# Sheet4.net
KiCad netlist of a schematic drawn in Altium Designer
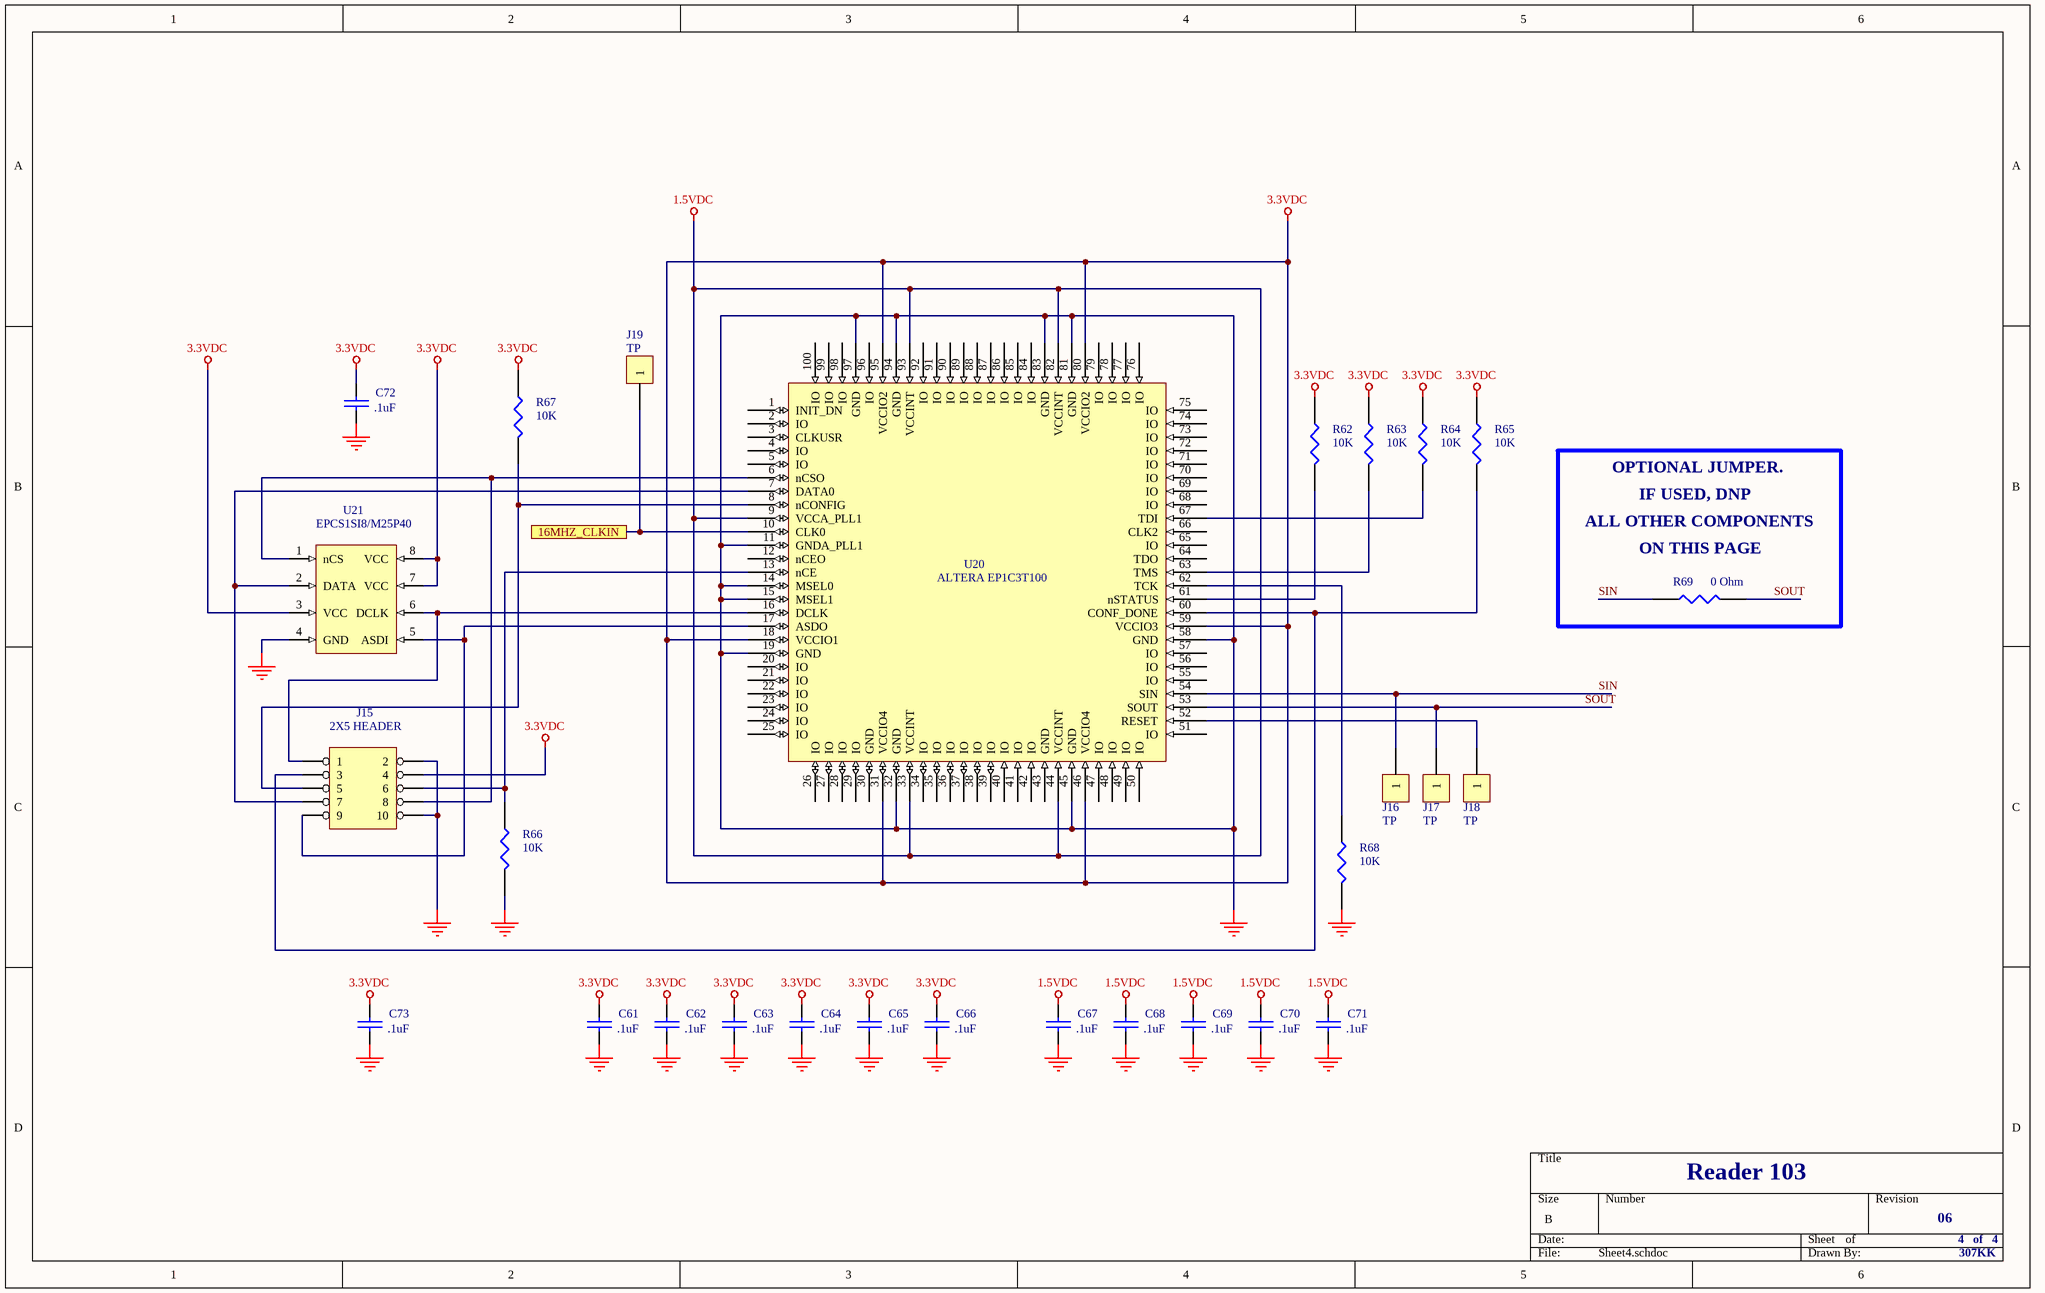
[diagram p0: Sheet4.schdoc]

(export (version "E")
  (design (tool "Eeschema 10.0.6"))
  (components
    (comp (ref "C61")
      (value ".1uF")
      (footprint "0603")
      (description "Capacitor")
      (libsource (lib "*") (part "CAP"))
    )
    (comp (ref "C62")
      (value ".1uF")
      (footprint "0603")
      (description "Capacitor")
      (libsource (lib "*") (part "CAP"))
    )
    (comp (ref "C63")
      (value ".1uF")
      (footprint "0603")
      (description "Capacitor")
      (libsource (lib "*") (part "CAP"))
    )
    (comp (ref "C64")
      (value ".1uF")
      (footprint "0603")
      (description "Capacitor")
      (libsource (lib "*") (part "CAP"))
    )
    (comp (ref "C65")
      (value ".1uF")
      (footprint "0603")
      (description "Capacitor")
      (libsource (lib "*") (part "CAP"))
    )
    (comp (ref "C66")
      (value ".1uF")
      (footprint "0603")
      (description "Capacitor")
      (libsource (lib "*") (part "CAP"))
    )
    (comp (ref "C67")
      (value ".1uF")
      (footprint "0603")
      (description "Capacitor")
      (libsource (lib "*") (part "CAP"))
    )
    (comp (ref "C68")
      (value ".1uF")
      (footprint "0603")
      (description "Capacitor")
      (libsource (lib "*") (part "CAP"))
    )
    (comp (ref "C69")
      (value ".1uF")
      (footprint "0603")
      (description "Capacitor")
      (libsource (lib "*") (part "CAP"))
    )
    (comp (ref "C70")
      (value ".1uF")
      (footprint "0603")
      (description "Capacitor")
      (libsource (lib "*") (part "CAP"))
    )
    (comp (ref "C71")
      (value ".1uF")
      (footprint "0603")
      (description "Capacitor")
      (libsource (lib "*") (part "CAP"))
    )
    (comp (ref "C72")
      (value ".1uF")
      (footprint "0603")
      (description "Capacitor")
      (libsource (lib "*") (part "CAP"))
    )
    (comp (ref "C73")
      (value ".1uF")
      (footprint "0603")
      (description "Capacitor")
      (libsource (lib "*") (part "CAP"))
    )
    (comp (ref "J15") (value "2X5 HEADER") (footprint "2X5 HEADER") (libsource (lib "*") (part "HEADER 5X2")))
    (comp (ref "J16")
      (value "TP")
      (footprint "TEST POINT PAD 3")
      (description "Connector")
      (libsource (lib "*") (part "CON1"))
    )
    (comp (ref "J17")
      (value "TP")
      (footprint "TEST POINT PAD 3")
      (description "Connector")
      (libsource (lib "*") (part "CON1"))
    )
    (comp (ref "J18")
      (value "TP")
      (footprint "TEST POINT PAD 3")
      (description "Connector")
      (libsource (lib "*") (part "CON1"))
    )
    (comp (ref "J19")
      (value "TP")
      (footprint "TEST POINT PAD 3")
      (description "Connector")
      (libsource (lib "") (part "CON1_1"))
    )
    (comp (ref "R62") (value "10K") (footprint "0603") (libsource (lib "*") (part "RES1")))
    (comp (ref "R63") (value "10K") (footprint "0603") (libsource (lib "*") (part "RES1")))
    (comp (ref "R64") (value "10K") (footprint "0603") (libsource (lib "*") (part "RES1")))
    (comp (ref "R65") (value "10K") (footprint "0603") (libsource (lib "*") (part "RES1")))
    (comp (ref "R66") (value "10K") (footprint "0603") (libsource (lib "*") (part "RES1")))
    (comp (ref "R67") (value "10K") (footprint "0603") (libsource (lib "*") (part "RES1")))
    (comp (ref "R68") (value "10K") (footprint "0603") (libsource (lib "*") (part "RES1")))
    (comp (ref "R69") (value "0 Ohm") (footprint "0603") (libsource (lib "*") (part "RES1")))
    (comp (ref "U20")
      (value "ALTERA EP1C3T100")
      (footprint "TQFP100")
      (libsource (lib "*") (part "ALTERA EP1C3T100"))
    )
    (comp (ref "U21")
      (value "EPCS1SI8/M25P40")
      (footprint "SO8")
      (libsource (lib "*") (part "EPCS1SI8/M25P40"))
    )
  )
  (nets
    (net (code "1") (name "/16MHZ_CLKIN") (class "Default")
      (node (ref "J19") (pin "1") (pinfunction "1_1") (pintype "passive"))
      (node (ref "U20") (pin "10") (pinfunction "CLK0_10") (pintype "bidirectional"))
    )
    (net (code "2") (name "/SIN") (class "Default")
      (node (ref "J16") (pin "1") (pinfunction "1_1") (pintype "passive"))
      (node (ref "R69") (pin "1") (pinfunction "1_1") (pintype "passive"))
      (node (ref "U20") (pin "54") (pinfunction "SIN_54") (pintype "input"))
    )
    (net (code "3") (name "/SOUT") (class "Default")
      (node (ref "J17") (pin "1") (pinfunction "1_1") (pintype "passive"))
      (node (ref "R69") (pin "2") (pinfunction "2_2") (pintype "passive"))
      (node (ref "U20") (pin "53") (pinfunction "SOUT_53") (pintype "input"))
    )
    (net (code "4") (name "1.5VDC") (class "Default")
      (node (ref "C67") (pin "1") (pinfunction "1_1") (pintype "passive"))
      (node (ref "C68") (pin "1") (pinfunction "1_1") (pintype "passive"))
      (node (ref "C69") (pin "1") (pinfunction "1_1") (pintype "passive"))
      (node (ref "C70") (pin "1") (pinfunction "1_1") (pintype "passive"))
      (node (ref "C71") (pin "1") (pinfunction "1_1") (pintype "passive"))
      (node (ref "U20") (pin "33") (pinfunction "VCCINT_33") (pintype "bidirectional"))
      (node (ref "U20") (pin "44") (pinfunction "VCCINT_44") (pintype "input"))
      (node (ref "U20") (pin "82") (pinfunction "VCCINT_82") (pintype "input"))
      (node (ref "U20") (pin "9") (pinfunction "VCCA_PLL1_9") (pintype "bidirectional"))
      (node (ref "U20") (pin "93") (pinfunction "VCCINT_93") (pintype "input"))
    )
    (net (code "5") (name "3.3VDC") (class "Default")
      (node (ref "C61") (pin "1") (pinfunction "1_1") (pintype "passive"))
      (node (ref "C62") (pin "1") (pinfunction "1_1") (pintype "passive"))
      (node (ref "C63") (pin "1") (pinfunction "1_1") (pintype "passive"))
      (node (ref "C64") (pin "1") (pinfunction "1_1") (pintype "passive"))
      (node (ref "C65") (pin "1") (pinfunction "1_1") (pintype "passive"))
      (node (ref "C66") (pin "1") (pinfunction "1_1") (pintype "passive"))
      (node (ref "C72") (pin "1") (pinfunction "1_1") (pintype "passive"))
      (node (ref "C73") (pin "1") (pinfunction "1_1") (pintype "passive"))
      (node (ref "J15") (pin "4") (pinfunction "4_4") (pintype "passive"))
      (node (ref "R62") (pin "1") (pinfunction "1_1") (pintype "passive"))
      (node (ref "R63") (pin "1") (pinfunction "1_1") (pintype "passive"))
      (node (ref "R64") (pin "1") (pinfunction "1_1") (pintype "passive"))
      (node (ref "R65") (pin "1") (pinfunction "1_1") (pintype "passive"))
      (node (ref "R67") (pin "1") (pinfunction "1_1") (pintype "passive"))
      (node (ref "U20") (pin "18") (pinfunction "VCCIO1_18") (pintype "bidirectional"))
      (node (ref "U20") (pin "31") (pinfunction "VCCIO4_31") (pintype "bidirectional"))
      (node (ref "U20") (pin "46") (pinfunction "VCCIO4_46") (pintype "input"))
      (node (ref "U20") (pin "59") (pinfunction "VCCIO3_59") (pintype "input"))
      (node (ref "U20") (pin "80") (pinfunction "VCCIO2_80") (pintype "input"))
      (node (ref "U20") (pin "95") (pinfunction "VCCIO2_95") (pintype "input"))
      (node (ref "U21") (pin "3") (pinfunction "VCC_3") (pintype "input"))
      (node (ref "U21") (pin "7") (pinfunction "VCC_7") (pintype "input"))
      (node (ref "U21") (pin "8") (pinfunction "VCC_8") (pintype "input"))
    )
    (net (code "6") (name "GND_COM") (class "Default")
      (node (ref "C61") (pin "2") (pinfunction "2_2") (pintype "passive"))
      (node (ref "C62") (pin "2") (pinfunction "2_2") (pintype "passive"))
      (node (ref "C63") (pin "2") (pinfunction "2_2") (pintype "passive"))
      (node (ref "C64") (pin "2") (pinfunction "2_2") (pintype "passive"))
      (node (ref "C65") (pin "2") (pinfunction "2_2") (pintype "passive"))
      (node (ref "C66") (pin "2") (pinfunction "2_2") (pintype "passive"))
      (node (ref "C67") (pin "2") (pinfunction "2_2") (pintype "passive"))
      (node (ref "C68") (pin "2") (pinfunction "2_2") (pintype "passive"))
      (node (ref "C69") (pin "2") (pinfunction "2_2") (pintype "passive"))
      (node (ref "C70") (pin "2") (pinfunction "2_2") (pintype "passive"))
      (node (ref "C71") (pin "2") (pinfunction "2_2") (pintype "passive"))
      (node (ref "C72") (pin "2") (pinfunction "2_2") (pintype "passive"))
      (node (ref "C73") (pin "2") (pinfunction "2_2") (pintype "passive"))
      (node (ref "J15") (pin "10") (pinfunction "10_10") (pintype "passive"))
      (node (ref "J15") (pin "2") (pinfunction "2_2") (pintype "passive"))
      (node (ref "R66") (pin "2") (pinfunction "2_2") (pintype "passive"))
      (node (ref "R68") (pin "2") (pinfunction "2_2") (pintype "passive"))
      (node (ref "U20") (pin "11") (pinfunction "GNDA_PLL1_11") (pintype "bidirectional"))
      (node (ref "U20") (pin "14") (pinfunction "MSEL0_14") (pintype "bidirectional"))
      (node (ref "U20") (pin "15") (pinfunction "MSEL1_15") (pintype "bidirectional"))
      (node (ref "U20") (pin "19") (pinfunction "GND_19") (pintype "bidirectional"))
      (node (ref "U20") (pin "32") (pinfunction "GND_32") (pintype "bidirectional"))
      (node (ref "U20") (pin "45") (pinfunction "GND_45") (pintype "input"))
      (node (ref "U20") (pin "58") (pinfunction "GND_58") (pintype "input"))
      (node (ref "U20") (pin "81") (pinfunction "GND_81") (pintype "input"))
      (node (ref "U20") (pin "83") (pinfunction "GND_83") (pintype "input"))
      (node (ref "U20") (pin "94") (pinfunction "GND_94") (pintype "input"))
      (node (ref "U20") (pin "97") (pinfunction "GND_97") (pintype "input"))
      (node (ref "U21") (pin "4") (pinfunction "GND_4") (pintype "input"))
    )
    (net (code "7") (name "Net-(U20-ASDO)") (class "Default")
      (node (ref "J15") (pin "9") (pinfunction "9_9") (pintype "passive"))
      (node (ref "U20") (pin "17") (pinfunction "ASDO_17") (pintype "bidirectional"))
      (node (ref "U21") (pin "5") (pinfunction "ASDI_5") (pintype "input"))
    )
    (net (code "8") (name "Net-(U20-CONF_DONE)") (class "Default")
      (node (ref "J15") (pin "3") (pinfunction "3_3") (pintype "passive"))
      (node (ref "R65") (pin "2") (pinfunction "2_2") (pintype "passive"))
      (node (ref "U20") (pin "60") (pinfunction "CONF_DONE_60") (pintype "input"))
    )
    (net (code "9") (name "Net-(U20-DATA0)") (class "Default")
      (node (ref "J15") (pin "7") (pinfunction "7_7") (pintype "passive"))
      (node (ref "U20") (pin "7") (pinfunction "DATA0_7") (pintype "bidirectional"))
      (node (ref "U21") (pin "2") (pinfunction "DATA_2") (pintype "input"))
    )
    (net (code "10") (name "Net-(U20-DCLK)") (class "Default")
      (node (ref "J15") (pin "1") (pinfunction "1_1") (pintype "passive"))
      (node (ref "U20") (pin "16") (pinfunction "DCLK_16") (pintype "bidirectional"))
      (node (ref "U21") (pin "6") (pinfunction "DCLK_6") (pintype "input"))
    )
    (net (code "11") (name "Net-(U20-RESET)") (class "Default")
      (node (ref "J18") (pin "1") (pinfunction "1_1") (pintype "passive"))
      (node (ref "U20") (pin "52") (pinfunction "RESET_52") (pintype "input"))
    )
    (net (code "12") (name "Net-(U20-TCK)") (class "Default")
      (node (ref "R68") (pin "1") (pinfunction "1_1") (pintype "passive"))
      (node (ref "U20") (pin "62") (pinfunction "TCK_62") (pintype "input"))
    )
    (net (code "13") (name "Net-(U20-TDI)") (class "Default")
      (node (ref "R64") (pin "2") (pinfunction "2_2") (pintype "passive"))
      (node (ref "U20") (pin "67") (pinfunction "TDI_67") (pintype "input"))
    )
    (net (code "14") (name "Net-(U20-TMS)") (class "Default")
      (node (ref "R63") (pin "2") (pinfunction "2_2") (pintype "passive"))
      (node (ref "U20") (pin "63") (pinfunction "TMS_63") (pintype "input"))
    )
    (net (code "15") (name "Net-(U20-nCE)") (class "Default")
      (node (ref "J15") (pin "6") (pinfunction "6_6") (pintype "passive"))
      (node (ref "R66") (pin "1") (pinfunction "1_1") (pintype "passive"))
      (node (ref "U20") (pin "13") (pinfunction "nCE_13") (pintype "bidirectional"))
    )
    (net (code "16") (name "Net-(U20-nCONFIG)") (class "Default")
      (node (ref "J15") (pin "5") (pinfunction "5_5") (pintype "passive"))
      (node (ref "R67") (pin "2") (pinfunction "2_2") (pintype "passive"))
      (node (ref "U20") (pin "8") (pinfunction "nCONFIG_8") (pintype "bidirectional"))
    )
    (net (code "17") (name "Net-(U20-nCSO)") (class "Default")
      (node (ref "J15") (pin "8") (pinfunction "8_8") (pintype "passive"))
      (node (ref "U20") (pin "6") (pinfunction "nCSO_6") (pintype "bidirectional"))
      (node (ref "U21") (pin "1") (pinfunction "nCS_1") (pintype "input"))
    )
    (net (code "18") (name "Net-(U20-nSTATUS)") (class "Default")
      (node (ref "R62") (pin "2") (pinfunction "2_2") (pintype "passive"))
      (node (ref "U20") (pin "61") (pinfunction "nSTATUS_61") (pintype "input"))
    )
    (net (code "19") (name "unconnected-(U20-CLK2-Pad66)") (class "Default")
      (node (ref "U20") (pin "66") (pinfunction "CLK2_66") (pintype "input"))
    )
    (net (code "20") (name "unconnected-(U20-CLKUSR-Pad3)") (class "Default")
      (node (ref "U20") (pin "3") (pinfunction "CLKUSR_3") (pintype "bidirectional"))
    )
    (net (code "21") (name "unconnected-(U20-GND-Pad30)") (class "Default")
      (node (ref "U20") (pin "30") (pinfunction "GND_30") (pintype "bidirectional"))
    )
    (net (code "22") (name "unconnected-(U20-GND-Pad43)") (class "Default")
      (node (ref "U20") (pin "43") (pinfunction "GND_43") (pintype "input"))
    )
    (net (code "23") (name "unconnected-(U20-INIT_DN-Pad1)") (class "Default")
      (node (ref "U20") (pin "1") (pinfunction "INIT_DN_1") (pintype "bidirectional"))
    )
    (net (code "24") (name "unconnected-(U20-IO-Pad2)") (class "Default")
      (node (ref "U20") (pin "2") (pinfunction "IO_2") (pintype "bidirectional"))
    )
    (net (code "25") (name "unconnected-(U20-IO-Pad4)") (class "Default")
      (node (ref "U20") (pin "4") (pinfunction "IO_4") (pintype "bidirectional"))
    )
    (net (code "26") (name "unconnected-(U20-IO-Pad5)") (class "Default")
      (node (ref "U20") (pin "5") (pinfunction "IO_5") (pintype "bidirectional"))
    )
    (net (code "27") (name "unconnected-(U20-IO-Pad20)") (class "Default")
      (node (ref "U20") (pin "20") (pinfunction "IO_20") (pintype "bidirectional"))
    )
    (net (code "28") (name "unconnected-(U20-IO-Pad21)") (class "Default")
      (node (ref "U20") (pin "21") (pinfunction "IO_21") (pintype "bidirectional"))
    )
    (net (code "29") (name "unconnected-(U20-IO-Pad22)") (class "Default")
      (node (ref "U20") (pin "22") (pinfunction "IO_22") (pintype "bidirectional"))
    )
    (net (code "30") (name "unconnected-(U20-IO-Pad23)") (class "Default")
      (node (ref "U20") (pin "23") (pinfunction "IO_23") (pintype "bidirectional"))
    )
    (net (code "31") (name "unconnected-(U20-IO-Pad24)") (class "Default")
      (node (ref "U20") (pin "24") (pinfunction "IO_24") (pintype "bidirectional"))
    )
    (net (code "32") (name "unconnected-(U20-IO-Pad25)") (class "Default")
      (node (ref "U20") (pin "25") (pinfunction "IO_25") (pintype "bidirectional"))
    )
    (net (code "33") (name "unconnected-(U20-IO-Pad26)") (class "Default")
      (node (ref "U20") (pin "26") (pinfunction "IO_26") (pintype "bidirectional"))
    )
    (net (code "34") (name "unconnected-(U20-IO-Pad27)") (class "Default")
      (node (ref "U20") (pin "27") (pinfunction "IO_27") (pintype "bidirectional"))
    )
    (net (code "35") (name "unconnected-(U20-IO-Pad28)") (class "Default")
      (node (ref "U20") (pin "28") (pinfunction "IO_28") (pintype "bidirectional"))
    )
    (net (code "36") (name "unconnected-(U20-IO-Pad29)") (class "Default")
      (node (ref "U20") (pin "29") (pinfunction "IO_29") (pintype "bidirectional"))
    )
    (net (code "37") (name "unconnected-(U20-IO-Pad34)") (class "Default")
      (node (ref "U20") (pin "34") (pinfunction "IO_34") (pintype "bidirectional"))
    )
    (net (code "38") (name "unconnected-(U20-IO-Pad35)") (class "Default")
      (node (ref "U20") (pin "35") (pinfunction "IO_35") (pintype "bidirectional"))
    )
    (net (code "39") (name "unconnected-(U20-IO-Pad36)") (class "Default")
      (node (ref "U20") (pin "36") (pinfunction "IO_36") (pintype "bidirectional"))
    )
    (net (code "40") (name "unconnected-(U20-IO-Pad37)") (class "Default")
      (node (ref "U20") (pin "37") (pinfunction "IO_37") (pintype "bidirectional"))
    )
    (net (code "41") (name "unconnected-(U20-IO-Pad38)") (class "Default")
      (node (ref "U20") (pin "38") (pinfunction "IO_38") (pintype "bidirectional"))
    )
    (net (code "42") (name "unconnected-(U20-IO-Pad39)") (class "Default")
      (node (ref "U20") (pin "39") (pinfunction "IO_39") (pintype "bidirectional"))
    )
    (net (code "43") (name "unconnected-(U20-IO-Pad40)") (class "Default")
      (node (ref "U20") (pin "40") (pinfunction "IO_40") (pintype "input"))
    )
    (net (code "44") (name "unconnected-(U20-IO-Pad41)") (class "Default")
      (node (ref "U20") (pin "41") (pinfunction "IO_41") (pintype "input"))
    )
    (net (code "45") (name "unconnected-(U20-IO-Pad42)") (class "Default")
      (node (ref "U20") (pin "42") (pinfunction "IO_42") (pintype "input"))
    )
    (net (code "46") (name "unconnected-(U20-IO-Pad47)") (class "Default")
      (node (ref "U20") (pin "47") (pinfunction "IO_47") (pintype "input"))
    )
    (net (code "47") (name "unconnected-(U20-IO-Pad48)") (class "Default")
      (node (ref "U20") (pin "48") (pinfunction "IO_48") (pintype "input"))
    )
    (net (code "48") (name "unconnected-(U20-IO-Pad49)") (class "Default")
      (node (ref "U20") (pin "49") (pinfunction "IO_49") (pintype "input"))
    )
    (net (code "49") (name "unconnected-(U20-IO-Pad50)") (class "Default")
      (node (ref "U20") (pin "50") (pinfunction "IO_50") (pintype "input"))
    )
    (net (code "50") (name "unconnected-(U20-IO-Pad51)") (class "Default")
      (node (ref "U20") (pin "51") (pinfunction "IO_51") (pintype "input"))
    )
    (net (code "51") (name "unconnected-(U20-IO-Pad55)") (class "Default")
      (node (ref "U20") (pin "55") (pinfunction "IO_55") (pintype "input"))
    )
    (net (code "52") (name "unconnected-(U20-IO-Pad56)") (class "Default")
      (node (ref "U20") (pin "56") (pinfunction "IO_56") (pintype "input"))
    )
    (net (code "53") (name "unconnected-(U20-IO-Pad57)") (class "Default")
      (node (ref "U20") (pin "57") (pinfunction "IO_57") (pintype "input"))
    )
    (net (code "54") (name "unconnected-(U20-IO-Pad65)") (class "Default")
      (node (ref "U20") (pin "65") (pinfunction "IO_65") (pintype "input"))
    )
    (net (code "55") (name "unconnected-(U20-IO-Pad68)") (class "Default")
      (node (ref "U20") (pin "68") (pinfunction "IO_68") (pintype "input"))
    )
    (net (code "56") (name "unconnected-(U20-IO-Pad69)") (class "Default")
      (node (ref "U20") (pin "69") (pinfunction "IO_69") (pintype "input"))
    )
    (net (code "57") (name "unconnected-(U20-IO-Pad70)") (class "Default")
      (node (ref "U20") (pin "70") (pinfunction "IO_70") (pintype "input"))
    )
    (net (code "58") (name "unconnected-(U20-IO-Pad71)") (class "Default")
      (node (ref "U20") (pin "71") (pinfunction "IO_71") (pintype "input"))
    )
    (net (code "59") (name "unconnected-(U20-IO-Pad72)") (class "Default")
      (node (ref "U20") (pin "72") (pinfunction "IO_72") (pintype "input"))
    )
    (net (code "60") (name "unconnected-(U20-IO-Pad73)") (class "Default")
      (node (ref "U20") (pin "73") (pinfunction "IO_73") (pintype "input"))
    )
    (net (code "61") (name "unconnected-(U20-IO-Pad74)") (class "Default")
      (node (ref "U20") (pin "74") (pinfunction "IO_74") (pintype "input"))
    )
    (net (code "62") (name "unconnected-(U20-IO-Pad75)") (class "Default")
      (node (ref "U20") (pin "75") (pinfunction "IO_75") (pintype "input"))
    )
    (net (code "63") (name "unconnected-(U20-IO-Pad76)") (class "Default")
      (node (ref "U20") (pin "76") (pinfunction "IO_76") (pintype "input"))
    )
    (net (code "64") (name "unconnected-(U20-IO-Pad77)") (class "Default")
      (node (ref "U20") (pin "77") (pinfunction "IO_77") (pintype "input"))
    )
    (net (code "65") (name "unconnected-(U20-IO-Pad78)") (class "Default")
      (node (ref "U20") (pin "78") (pinfunction "IO_78") (pintype "input"))
    )
    (net (code "66") (name "unconnected-(U20-IO-Pad79)") (class "Default")
      (node (ref "U20") (pin "79") (pinfunction "IO_79") (pintype "input"))
    )
    (net (code "67") (name "unconnected-(U20-IO-Pad84)") (class "Default")
      (node (ref "U20") (pin "84") (pinfunction "IO_84") (pintype "input"))
    )
    (net (code "68") (name "unconnected-(U20-IO-Pad85)") (class "Default")
      (node (ref "U20") (pin "85") (pinfunction "IO_85") (pintype "input"))
    )
    (net (code "69") (name "unconnected-(U20-IO-Pad86)") (class "Default")
      (node (ref "U20") (pin "86") (pinfunction "IO_86") (pintype "input"))
    )
    (net (code "70") (name "unconnected-(U20-IO-Pad87)") (class "Default")
      (node (ref "U20") (pin "87") (pinfunction "IO_87") (pintype "input"))
    )
    (net (code "71") (name "unconnected-(U20-IO-Pad88)") (class "Default")
      (node (ref "U20") (pin "88") (pinfunction "IO_88") (pintype "input"))
    )
    (net (code "72") (name "unconnected-(U20-IO-Pad89)") (class "Default")
      (node (ref "U20") (pin "89") (pinfunction "IO_89") (pintype "input"))
    )
    (net (code "73") (name "unconnected-(U20-IO-Pad90)") (class "Default")
      (node (ref "U20") (pin "90") (pinfunction "IO_90") (pintype "input"))
    )
    (net (code "74") (name "unconnected-(U20-IO-Pad91)") (class "Default")
      (node (ref "U20") (pin "91") (pinfunction "IO_91") (pintype "input"))
    )
    (net (code "75") (name "unconnected-(U20-IO-Pad92)") (class "Default")
      (node (ref "U20") (pin "92") (pinfunction "IO_92") (pintype "input"))
    )
    (net (code "76") (name "unconnected-(U20-IO-Pad96)") (class "Default")
      (node (ref "U20") (pin "96") (pinfunction "IO_96") (pintype "input"))
    )
    (net (code "77") (name "unconnected-(U20-IO-Pad98)") (class "Default")
      (node (ref "U20") (pin "98") (pinfunction "IO_98") (pintype "input"))
    )
    (net (code "78") (name "unconnected-(U20-IO-Pad99)") (class "Default")
      (node (ref "U20") (pin "99") (pinfunction "IO_99") (pintype "input"))
    )
    (net (code "79") (name "unconnected-(U20-IO-Pad100)") (class "Default")
      (node (ref "U20") (pin "100") (pinfunction "IO_100") (pintype "input"))
    )
    (net (code "80") (name "unconnected-(U20-TDO-Pad64)") (class "Default")
      (node (ref "U20") (pin "64") (pinfunction "TDO_64") (pintype "input"))
    )
    (net (code "81") (name "unconnected-(U20-nCEO-Pad12)") (class "Default")
      (node (ref "U20") (pin "12") (pinfunction "nCEO_12") (pintype "bidirectional"))
    )
  )
)
